# DDR3.net
KiCad netlist of a schematic drawn in Altium Designer
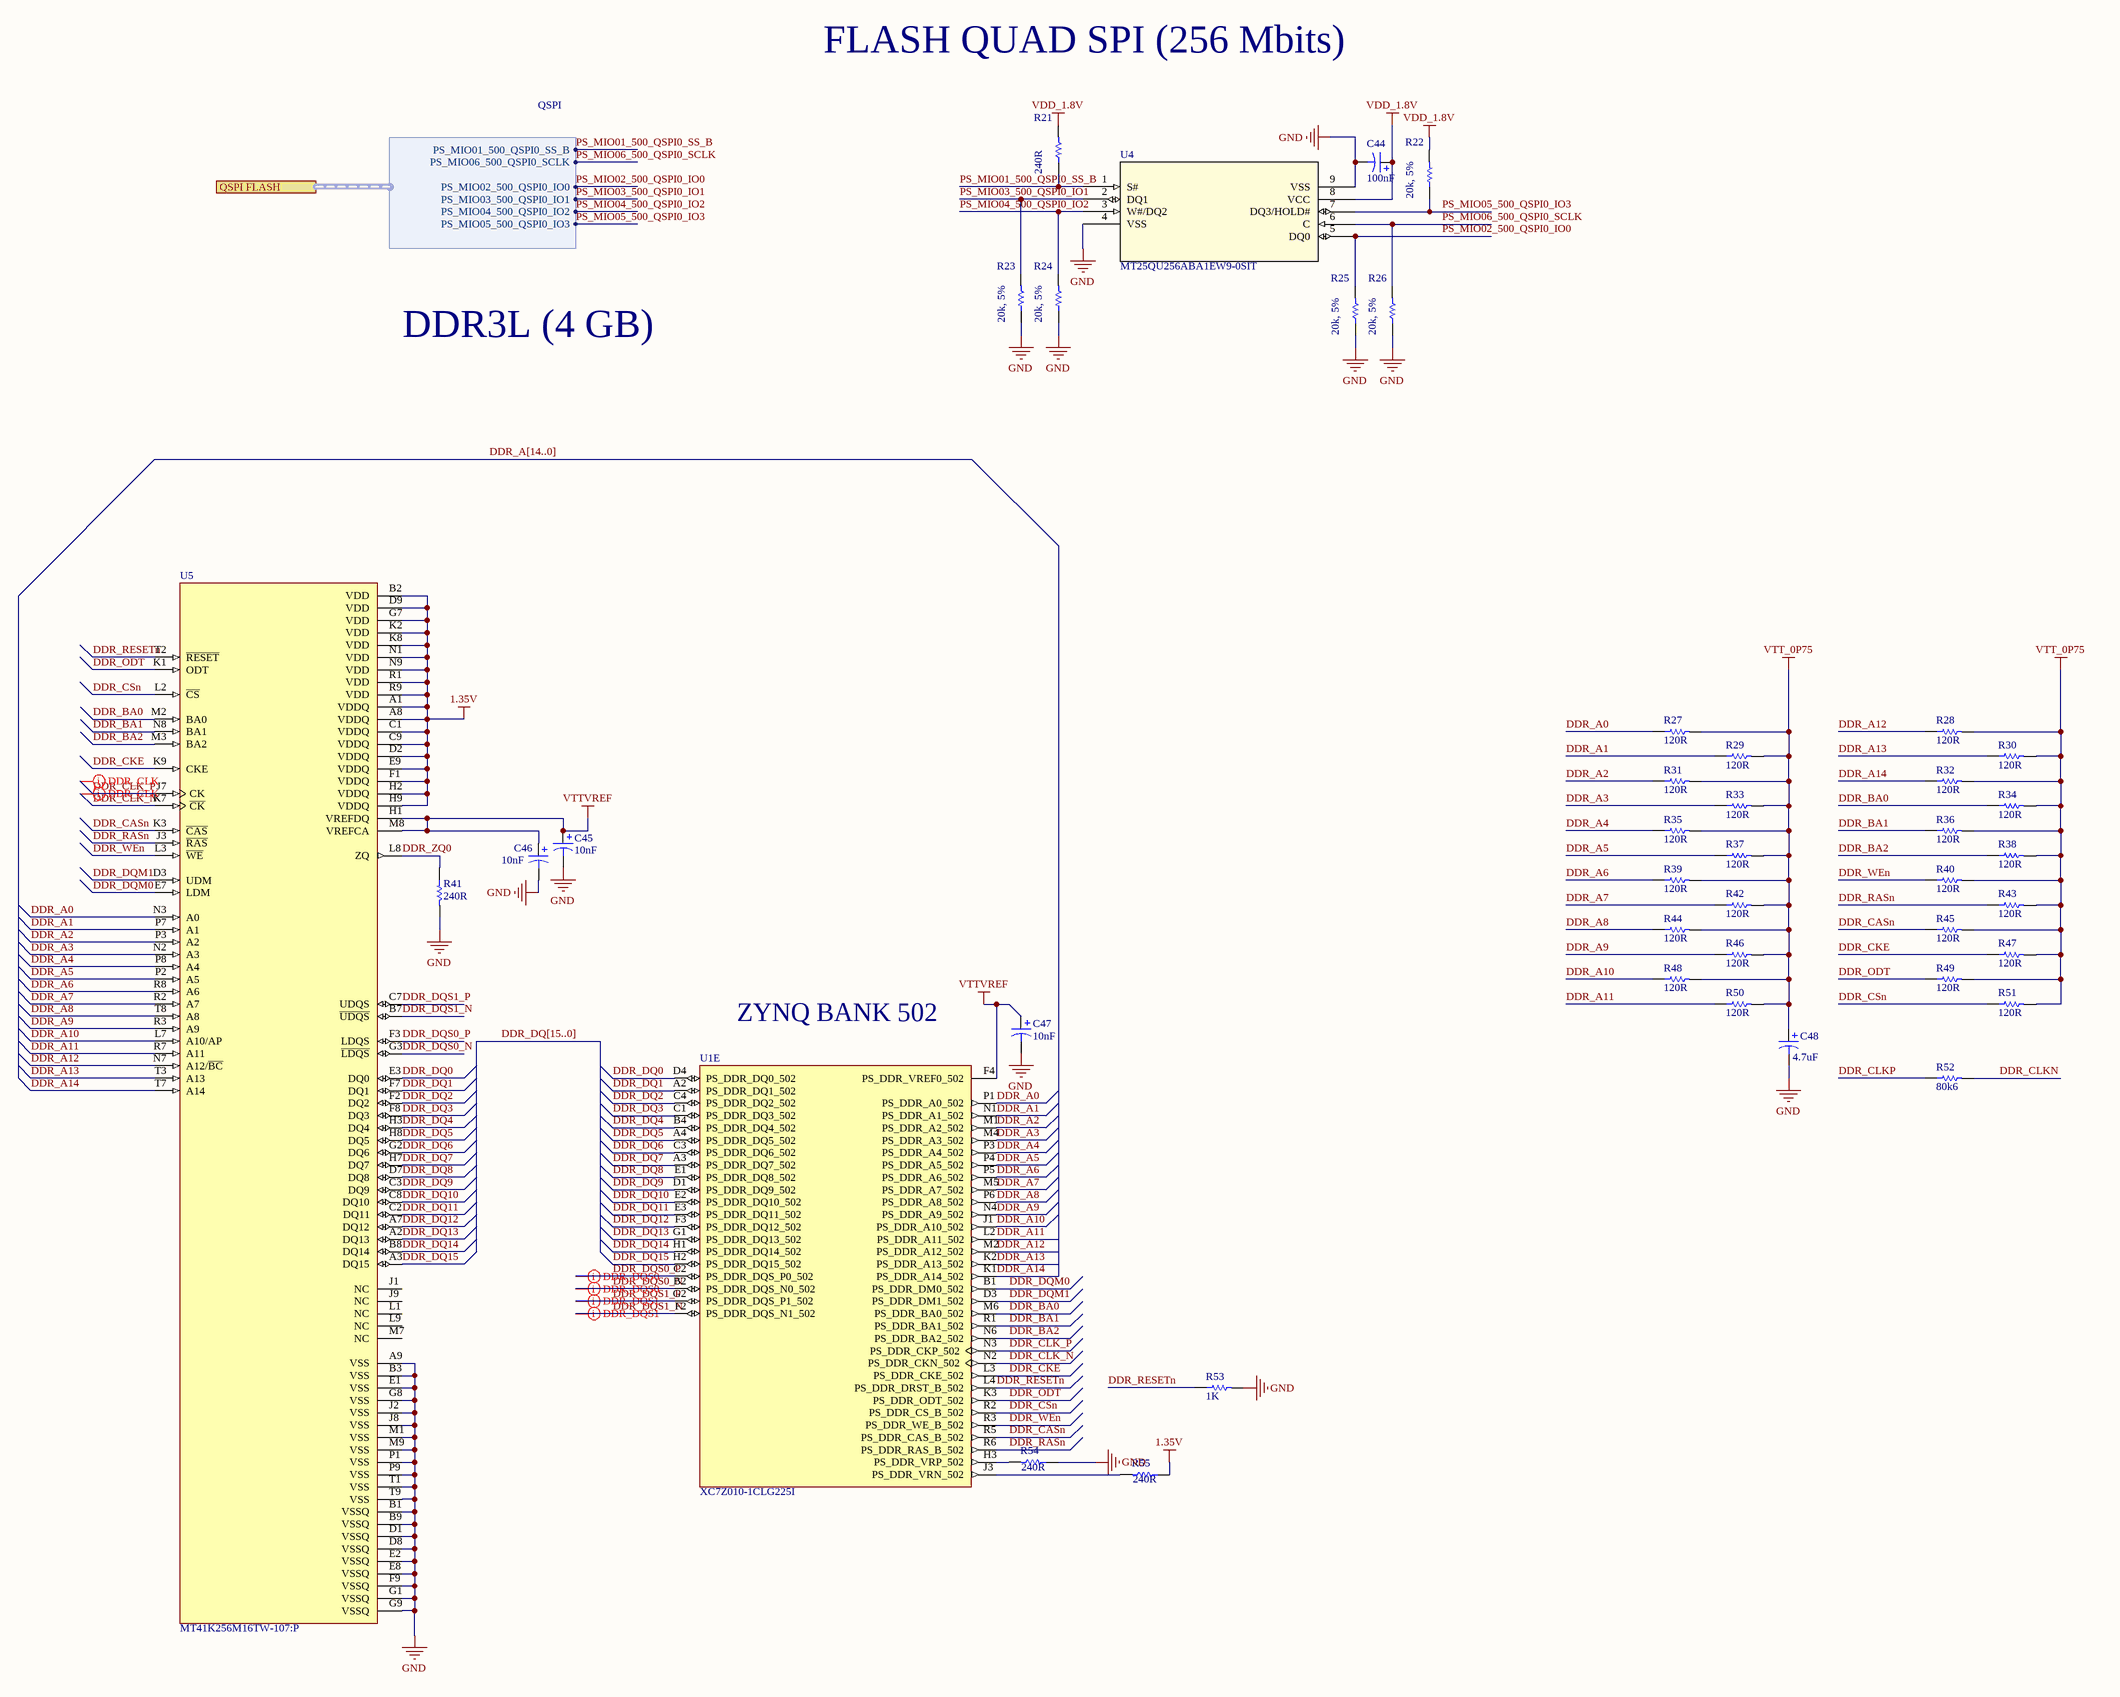
[diagram p0: DDR3.SchDoc]

(export (version "E")
  (design (tool "Eeschema 10.0.6"))
  (components
    (comp (ref "C44")
      (value "100nF")
      (footprint "C0805")
      (description "Polarized Capacitor (Surface Mount)")
      (fields (field (name "Comment") "Cap Pol3") (field (name "PUBLISHER") "Altium Limited"))
      (libsource (lib "Miscellaneous Devices") (part "Cap Pol3"))
    )
    (comp (ref "C45")
      (value "10nF")
      (footprint "C0805")
      (description "Polarized Capacitor (Surface Mount)")
      (fields (field (name "Comment") "Cap Pol3") (field (name "PUBLISHER") "Altium Limited"))
      (libsource (lib "Miscellaneous Devices") (part "Cap Pol3"))
    )
    (comp (ref "C46")
      (value "10nF")
      (footprint "C0805")
      (description "Polarized Capacitor (Surface Mount)")
      (fields (field (name "Comment") "Cap Pol3") (field (name "PUBLISHER") "Altium Limited"))
      (libsource (lib "Miscellaneous Devices") (part "Cap Pol3"))
    )
    (comp (ref "C47")
      (value "10nF")
      (footprint "C0805")
      (description "Polarized Capacitor (Surface Mount)")
      (fields (field (name "Comment") "Cap Pol3") (field (name "PUBLISHER") "Altium Limited"))
      (libsource (lib "Miscellaneous Devices") (part "Cap Pol3"))
    )
    (comp (ref "C48")
      (value "4.7uF")
      (footprint "C0805")
      (description "Polarized Capacitor (Surface Mount)")
      (fields (field (name "Comment") "Cap Pol3") (field (name "PUBLISHER") "Altium Limited"))
      (libsource (lib "Miscellaneous Devices") (part "Cap Pol3"))
    )
    (comp (ref "R21")
      (value "240R")
      (footprint "0603")
      (description "Resistor")
      (fields
        (field (name "MANUFACTURER") "Generic Components")
        (field (name "Comment") "Res1")
        (field (name "PUBLISHER") "Altium Limited")
      )
      (libsource (lib "lib_protel_HC") (part "Res1_1"))
    )
    (comp (ref "R22")
      (value "20k, 5%")
      (footprint "0603")
      (description "Resistor")
      (fields
        (field (name "MANUFACTURER") "Generic Components")
        (field (name "Comment") "Res1")
        (field (name "PUBLISHER") "Altium Limited")
      )
      (libsource (lib "lib_protel_HC") (part "Res1_1"))
    )
    (comp (ref "R23")
      (value "20k, 5%")
      (footprint "0603")
      (description "Resistor")
      (fields
        (field (name "MANUFACTURER") "Generic Components")
        (field (name "Comment") "Res1")
        (field (name "PUBLISHER") "Altium Limited")
      )
      (libsource (lib "lib_protel_HC") (part "Res1_1"))
    )
    (comp (ref "R24")
      (value "20k, 5%")
      (footprint "0603")
      (description "Resistor")
      (fields
        (field (name "MANUFACTURER") "Generic Components")
        (field (name "Comment") "Res1")
        (field (name "PUBLISHER") "Altium Limited")
      )
      (libsource (lib "lib_protel_HC") (part "Res1_1"))
    )
    (comp (ref "R25")
      (value "20k, 5%")
      (footprint "0603")
      (description "Resistor")
      (fields
        (field (name "MANUFACTURER") "Generic Components")
        (field (name "Comment") "Res1")
        (field (name "PUBLISHER") "Altium Limited")
      )
      (libsource (lib "lib_protel_HC") (part "Res1_1"))
    )
    (comp (ref "R26")
      (value "20k, 5%")
      (footprint "0603")
      (description "Resistor")
      (fields
        (field (name "MANUFACTURER") "Generic Components")
        (field (name "Comment") "Res1")
        (field (name "PUBLISHER") "Altium Limited")
      )
      (libsource (lib "lib_protel_HC") (part "Res1_1"))
    )
    (comp (ref "R27")
      (value "120R")
      (footprint "0603")
      (description "Resistor")
      (fields
        (field (name "MANUFACTURER") "Generic Components")
        (field (name "Comment") "Res1")
        (field (name "PUBLISHER") "Altium Limited")
      )
      (libsource (lib "lib_protel_HC") (part "Res1_1"))
    )
    (comp (ref "R28")
      (value "120R")
      (footprint "0603")
      (description "Resistor")
      (fields
        (field (name "MANUFACTURER") "Generic Components")
        (field (name "Comment") "Res1")
        (field (name "PUBLISHER") "Altium Limited")
      )
      (libsource (lib "lib_protel_HC") (part "Res1_1"))
    )
    (comp (ref "R29")
      (value "120R")
      (footprint "0603")
      (description "Resistor")
      (fields
        (field (name "MANUFACTURER") "Generic Components")
        (field (name "Comment") "Res1")
        (field (name "PUBLISHER") "Altium Limited")
      )
      (libsource (lib "lib_protel_HC") (part "Res1_1"))
    )
    (comp (ref "R30")
      (value "120R")
      (footprint "0603")
      (description "Resistor")
      (fields
        (field (name "MANUFACTURER") "Generic Components")
        (field (name "Comment") "Res1")
        (field (name "PUBLISHER") "Altium Limited")
      )
      (libsource (lib "lib_protel_HC") (part "Res1_1"))
    )
    (comp (ref "R31")
      (value "120R")
      (footprint "0603")
      (description "Resistor")
      (fields
        (field (name "MANUFACTURER") "Generic Components")
        (field (name "Comment") "Res1")
        (field (name "PUBLISHER") "Altium Limited")
      )
      (libsource (lib "lib_protel_HC") (part "Res1_1"))
    )
    (comp (ref "R32")
      (value "120R")
      (footprint "0603")
      (description "Resistor")
      (fields
        (field (name "MANUFACTURER") "Generic Components")
        (field (name "Comment") "Res1")
        (field (name "PUBLISHER") "Altium Limited")
      )
      (libsource (lib "lib_protel_HC") (part "Res1_1"))
    )
    (comp (ref "R33")
      (value "120R")
      (footprint "0603")
      (description "Resistor")
      (fields
        (field (name "MANUFACTURER") "Generic Components")
        (field (name "Comment") "Res1")
        (field (name "PUBLISHER") "Altium Limited")
      )
      (libsource (lib "lib_protel_HC") (part "Res1_1"))
    )
    (comp (ref "R34")
      (value "120R")
      (footprint "0603")
      (description "Resistor")
      (fields
        (field (name "MANUFACTURER") "Generic Components")
        (field (name "Comment") "Res1")
        (field (name "PUBLISHER") "Altium Limited")
      )
      (libsource (lib "lib_protel_HC") (part "Res1_1"))
    )
    (comp (ref "R35")
      (value "120R")
      (footprint "0603")
      (description "Resistor")
      (fields
        (field (name "MANUFACTURER") "Generic Components")
        (field (name "Comment") "Res1")
        (field (name "PUBLISHER") "Altium Limited")
      )
      (libsource (lib "lib_protel_HC") (part "Res1_1"))
    )
    (comp (ref "R36")
      (value "120R")
      (footprint "0603")
      (description "Resistor")
      (fields
        (field (name "MANUFACTURER") "Generic Components")
        (field (name "Comment") "Res1")
        (field (name "PUBLISHER") "Altium Limited")
      )
      (libsource (lib "lib_protel_HC") (part "Res1_1"))
    )
    (comp (ref "R37")
      (value "120R")
      (footprint "0603")
      (description "Resistor")
      (fields
        (field (name "MANUFACTURER") "Generic Components")
        (field (name "Comment") "Res1")
        (field (name "PUBLISHER") "Altium Limited")
      )
      (libsource (lib "lib_protel_HC") (part "Res1_1"))
    )
    (comp (ref "R38")
      (value "120R")
      (footprint "0603")
      (description "Resistor")
      (fields
        (field (name "MANUFACTURER") "Generic Components")
        (field (name "Comment") "Res1")
        (field (name "PUBLISHER") "Altium Limited")
      )
      (libsource (lib "lib_protel_HC") (part "Res1_1"))
    )
    (comp (ref "R39")
      (value "120R")
      (footprint "0603")
      (description "Resistor")
      (fields
        (field (name "MANUFACTURER") "Generic Components")
        (field (name "Comment") "Res1")
        (field (name "PUBLISHER") "Altium Limited")
      )
      (libsource (lib "lib_protel_HC") (part "Res1_1"))
    )
    (comp (ref "R40")
      (value "120R")
      (footprint "0603")
      (description "Resistor")
      (fields
        (field (name "MANUFACTURER") "Generic Components")
        (field (name "Comment") "Res1")
        (field (name "PUBLISHER") "Altium Limited")
      )
      (libsource (lib "lib_protel_HC") (part "Res1_1"))
    )
    (comp (ref "R41")
      (value "240R")
      (footprint "0603")
      (description "Resistor")
      (fields
        (field (name "MANUFACTURER") "Generic Components")
        (field (name "Comment") "Res1")
        (field (name "PUBLISHER") "Altium Limited")
      )
      (libsource (lib "lib_protel_HC") (part "Res1_1"))
    )
    (comp (ref "R42")
      (value "120R")
      (footprint "0603")
      (description "Resistor")
      (fields
        (field (name "MANUFACTURER") "Generic Components")
        (field (name "Comment") "Res1")
        (field (name "PUBLISHER") "Altium Limited")
      )
      (libsource (lib "lib_protel_HC") (part "Res1_1"))
    )
    (comp (ref "R43")
      (value "120R")
      (footprint "0603")
      (description "Resistor")
      (fields
        (field (name "MANUFACTURER") "Generic Components")
        (field (name "Comment") "Res1")
        (field (name "PUBLISHER") "Altium Limited")
      )
      (libsource (lib "lib_protel_HC") (part "Res1_1"))
    )
    (comp (ref "R44")
      (value "120R")
      (footprint "0603")
      (description "Resistor")
      (fields
        (field (name "MANUFACTURER") "Generic Components")
        (field (name "Comment") "Res1")
        (field (name "PUBLISHER") "Altium Limited")
      )
      (libsource (lib "lib_protel_HC") (part "Res1_1"))
    )
    (comp (ref "R45")
      (value "120R")
      (footprint "0603")
      (description "Resistor")
      (fields
        (field (name "MANUFACTURER") "Generic Components")
        (field (name "Comment") "Res1")
        (field (name "PUBLISHER") "Altium Limited")
      )
      (libsource (lib "lib_protel_HC") (part "Res1_1"))
    )
    (comp (ref "R46")
      (value "120R")
      (footprint "0603")
      (description "Resistor")
      (fields
        (field (name "MANUFACTURER") "Generic Components")
        (field (name "Comment") "Res1")
        (field (name "PUBLISHER") "Altium Limited")
      )
      (libsource (lib "lib_protel_HC") (part "Res1_1"))
    )
    (comp (ref "R47")
      (value "120R")
      (footprint "0603")
      (description "Resistor")
      (fields
        (field (name "MANUFACTURER") "Generic Components")
        (field (name "Comment") "Res1")
        (field (name "PUBLISHER") "Altium Limited")
      )
      (libsource (lib "lib_protel_HC") (part "Res1_1"))
    )
    (comp (ref "R48")
      (value "120R")
      (footprint "0603")
      (description "Resistor")
      (fields
        (field (name "MANUFACTURER") "Generic Components")
        (field (name "Comment") "Res1")
        (field (name "PUBLISHER") "Altium Limited")
      )
      (libsource (lib "lib_protel_HC") (part "Res1_1"))
    )
    (comp (ref "R49")
      (value "120R")
      (footprint "0603")
      (description "Resistor")
      (fields
        (field (name "MANUFACTURER") "Generic Components")
        (field (name "Comment") "Res1")
        (field (name "PUBLISHER") "Altium Limited")
      )
      (libsource (lib "lib_protel_HC") (part "Res1_1"))
    )
    (comp (ref "R50")
      (value "120R")
      (footprint "0603")
      (description "Resistor")
      (fields
        (field (name "MANUFACTURER") "Generic Components")
        (field (name "Comment") "Res1")
        (field (name "PUBLISHER") "Altium Limited")
      )
      (libsource (lib "lib_protel_HC") (part "Res1_1"))
    )
    (comp (ref "R51")
      (value "120R")
      (footprint "0603")
      (description "Resistor")
      (fields
        (field (name "MANUFACTURER") "Generic Components")
        (field (name "Comment") "Res1")
        (field (name "PUBLISHER") "Altium Limited")
      )
      (libsource (lib "lib_protel_HC") (part "Res1_1"))
    )
    (comp (ref "R52")
      (value "80k6")
      (footprint "0603")
      (description "Resistor")
      (fields
        (field (name "MANUFACTURER") "Generic Components")
        (field (name "Comment") "Res1")
        (field (name "PUBLISHER") "Altium Limited")
      )
      (libsource (lib "lib_protel_HC") (part "Res1_1"))
    )
    (comp (ref "R53")
      (value "1K")
      (footprint "0603")
      (description "Resistor")
      (fields
        (field (name "MANUFACTURER") "Generic Components")
        (field (name "Comment") "Res1")
        (field (name "PUBLISHER") "Altium Limited")
      )
      (libsource (lib "lib_protel_HC") (part "Res1_1"))
    )
    (comp (ref "R54")
      (value "240R")
      (footprint "0603")
      (description "Resistor")
      (fields
        (field (name "MANUFACTURER") "Generic Components")
        (field (name "Comment") "Res1")
        (field (name "PUBLISHER") "Altium Limited")
      )
      (libsource (lib "lib_protel_HC") (part "Res1_1"))
    )
    (comp (ref "R55")
      (value "240R")
      (footprint "0603")
      (description "Resistor")
      (fields
        (field (name "MANUFACTURER") "Generic Components")
        (field (name "Comment") "Res1")
        (field (name "PUBLISHER") "Altium Limited")
      )
      (libsource (lib "lib_protel_HC") (part "Res1_1"))
    )
    (comp (ref "U1")
      (value "XC7Z010-1CLG225I")
      (footprint "BGA225C80P15X15_1300X1300X150N")
      (fields (field (name "MF") "Xilinx Inc."))
      (libsource (lib "XC7Z010-1CLG225I") (part "XC7Z010-1CLG225I"))
    )
    (comp (ref "U4")
      (value "MT25QU256ABA1EW9-0SIT")
      (footprint "W-PDFN-8MLP8_8X6_MRN")
      (description "No Description Available")
      (libsource (lib "MT25QU256ABA1EW9-0SIT") (part "MT25QU256ABA1EW9-0SIT"))
    )
    (comp (ref "U5")
      (value "MT41K256M16TW-107:P")
      (footprint "BGA96C80P9X16_1400X800X120")
      (fields (field (name "MF") "{'manufacturer': u'Micron Technology Inc.'}"))
      (libsource (lib "MT41K256M16TW-107_P") (part "MT41K256M16TW-107{colon}P"))
    )
  )
  (nets
    (net (code "2") (name "/DDR_A0") (class "Default")
      (node (ref "R27") (pin "1") (pinfunction "1_1") (pintype "passive"))
      (node (ref "U1") (pin "P1") (pinfunction "PS_DDR_A0_502_P1") (pintype "output"))
      (node (ref "U5") (pin "N3") (pinfunction "A0_N3") (pintype "input"))
    )
    (net (code "3") (name "/DDR_A1") (class "Default")
      (node (ref "R29") (pin "1") (pinfunction "1_1") (pintype "passive"))
      (node (ref "U1") (pin "N1") (pinfunction "PS_DDR_A1_502_N1") (pintype "output"))
      (node (ref "U5") (pin "P7") (pinfunction "A1_P7") (pintype "input"))
    )
    (net (code "4") (name "/DDR_A2") (class "Default")
      (node (ref "R31") (pin "1") (pinfunction "1_1") (pintype "passive"))
      (node (ref "U1") (pin "M1") (pinfunction "PS_DDR_A2_502_M1") (pintype "output"))
      (node (ref "U5") (pin "P3") (pinfunction "A2_P3") (pintype "input"))
    )
    (net (code "5") (name "/DDR_A3") (class "Default")
      (node (ref "R33") (pin "1") (pinfunction "1_1") (pintype "passive"))
      (node (ref "U1") (pin "M4") (pinfunction "PS_DDR_A3_502_M4") (pintype "output"))
      (node (ref "U5") (pin "N2") (pinfunction "A3_N2") (pintype "input"))
    )
    (net (code "6") (name "/DDR_A4") (class "Default")
      (node (ref "R35") (pin "1") (pinfunction "1_1") (pintype "passive"))
      (node (ref "U1") (pin "P3") (pinfunction "PS_DDR_A4_502_P3") (pintype "output"))
      (node (ref "U5") (pin "P8") (pinfunction "A4_P8") (pintype "input"))
    )
    (net (code "7") (name "/DDR_A5") (class "Default")
      (node (ref "R37") (pin "1") (pinfunction "1_1") (pintype "passive"))
      (node (ref "U1") (pin "P4") (pinfunction "PS_DDR_A5_502_P4") (pintype "output"))
      (node (ref "U5") (pin "P2") (pinfunction "A5_P2") (pintype "input"))
    )
    (net (code "8") (name "/DDR_A6") (class "Default")
      (node (ref "R39") (pin "1") (pinfunction "1_1") (pintype "passive"))
      (node (ref "U1") (pin "P5") (pinfunction "PS_DDR_A6_502_P5") (pintype "output"))
      (node (ref "U5") (pin "R8") (pinfunction "A6_R8") (pintype "input"))
    )
    (net (code "9") (name "/DDR_A7") (class "Default")
      (node (ref "R42") (pin "1") (pinfunction "1_1") (pintype "passive"))
      (node (ref "U1") (pin "M5") (pinfunction "PS_DDR_A7_502_M5") (pintype "output"))
      (node (ref "U5") (pin "R2") (pinfunction "A7_R2") (pintype "input"))
    )
    (net (code "10") (name "/DDR_A8") (class "Default")
      (node (ref "R44") (pin "1") (pinfunction "1_1") (pintype "passive"))
      (node (ref "U1") (pin "P6") (pinfunction "PS_DDR_A8_502_P6") (pintype "output"))
      (node (ref "U5") (pin "T8") (pinfunction "A8_T8") (pintype "input"))
    )
    (net (code "11") (name "/DDR_A9") (class "Default")
      (node (ref "R46") (pin "1") (pinfunction "1_1") (pintype "passive"))
      (node (ref "U1") (pin "N4") (pinfunction "PS_DDR_A9_502_N4") (pintype "output"))
      (node (ref "U5") (pin "R3") (pinfunction "A9_R3") (pintype "input"))
    )
    (net (code "12") (name "/DDR_A10") (class "Default")
      (node (ref "R48") (pin "1") (pinfunction "1_1") (pintype "passive"))
      (node (ref "U1") (pin "J1") (pinfunction "PS_DDR_A10_502_J1") (pintype "output"))
      (node (ref "U5") (pin "L7") (pinfunction "A10/AP_L7") (pintype "input"))
    )
    (net (code "13") (name "/DDR_A11") (class "Default")
      (node (ref "R50") (pin "1") (pinfunction "1_1") (pintype "passive"))
      (node (ref "U1") (pin "L2") (pinfunction "PS_DDR_A11_502_L2") (pintype "output"))
      (node (ref "U5") (pin "R7") (pinfunction "A11_R7") (pintype "input"))
    )
    (net (code "14") (name "/DDR_A12") (class "Default")
      (node (ref "R28") (pin "1") (pinfunction "1_1") (pintype "passive"))
      (node (ref "U1") (pin "M2") (pinfunction "PS_DDR_A12_502_M2") (pintype "output"))
      (node (ref "U5") (pin "N7") (pinfunction "A12/~{BC}_N7") (pintype "input"))
    )
    (net (code "15") (name "/DDR_A13") (class "Default")
      (node (ref "R30") (pin "1") (pinfunction "1_1") (pintype "passive"))
      (node (ref "U1") (pin "K2") (pinfunction "PS_DDR_A13_502_K2") (pintype "output"))
      (node (ref "U5") (pin "T3") (pinfunction "A13_T3") (pintype "input"))
    )
    (net (code "16") (name "/DDR_A14") (class "Default")
      (node (ref "R32") (pin "1") (pinfunction "1_1") (pintype "passive"))
      (node (ref "U1") (pin "K1") (pinfunction "PS_DDR_A14_502_K1") (pintype "output"))
      (node (ref "U5") (pin "T7") (pinfunction "A14_T7") (pintype "input"))
    )
    (net (code "18") (name "/DDR_BA0") (class "Default")
      (node (ref "R34") (pin "1") (pinfunction "1_1") (pintype "passive"))
      (node (ref "U1") (pin "M6") (pinfunction "PS_DDR_BA0_502_M6") (pintype "output"))
      (node (ref "U5") (pin "M2") (pinfunction "BA0_M2") (pintype "input"))
    )
    (net (code "19") (name "/DDR_BA1") (class "Default")
      (node (ref "R36") (pin "1") (pinfunction "1_1") (pintype "passive"))
      (node (ref "U1") (pin "R1") (pinfunction "PS_DDR_BA1_502_R1") (pintype "output"))
      (node (ref "U5") (pin "N8") (pinfunction "BA1_N8") (pintype "input"))
    )
    (net (code "20") (name "/DDR_BA2") (class "Default")
      (node (ref "R38") (pin "1") (pinfunction "1_1") (pintype "passive"))
      (node (ref "U1") (pin "N6") (pinfunction "PS_DDR_BA2_502_N6") (pintype "output"))
      (node (ref "U5") (pin "M3") (pinfunction "BA2_M3") (pintype "input"))
    )
    (net (code "21") (name "/DDR_CASn") (class "Default")
      (node (ref "R45") (pin "1") (pinfunction "1_1") (pintype "passive"))
      (node (ref "U1") (pin "R5") (pinfunction "PS_DDR_CAS_B_502_R5") (pintype "output"))
      (node (ref "U5") (pin "K3") (pinfunction "~{CAS}_K3") (pintype "input"))
    )
    (net (code "22") (name "/DDR_CKE") (class "Default")
      (node (ref "R47") (pin "1") (pinfunction "1_1") (pintype "passive"))
      (node (ref "U1") (pin "L3") (pinfunction "PS_DDR_CKE_502_L3") (pintype "output"))
      (node (ref "U5") (pin "K9") (pinfunction "CKE_K9") (pintype "input"))
    )
    (net (code "23") (name "/DDR_CLKN") (class "Default")
      (node (ref "R52") (pin "2") (pinfunction "2_2") (pintype "passive"))
    )
    (net (code "24") (name "/DDR_CLKP") (class "Default")
      (node (ref "R52") (pin "1") (pinfunction "1_1") (pintype "passive"))
    )
    (net (code "25") (name "/DDR_CLK_N") (class "Default")
      (node (ref "U1") (pin "N2") (pinfunction "PS_DDR_CKN_502_N2") (pintype "output"))
      (node (ref "U5") (pin "K7") (pinfunction "~{CK}_K7") (pintype "input"))
    )
    (net (code "26") (name "/DDR_CLK_P") (class "Default")
      (node (ref "U1") (pin "N3") (pinfunction "PS_DDR_CKP_502_N3") (pintype "output"))
      (node (ref "U5") (pin "J7") (pinfunction "CK_J7") (pintype "input"))
    )
    (net (code "27") (name "/DDR_CSn") (class "Default")
      (node (ref "R51") (pin "1") (pinfunction "1_1") (pintype "passive"))
      (node (ref "U1") (pin "R2") (pinfunction "PS_DDR_CS_B_502_R2") (pintype "output"))
      (node (ref "U5") (pin "L2") (pinfunction "~{CS}_L2") (pintype "input"))
    )
    (net (code "28") (name "/DDR_DQ0") (class "Default")
      (node (ref "U1") (pin "D4") (pinfunction "PS_DDR_DQ0_502_D4") (pintype "bidirectional"))
      (node (ref "U5") (pin "E3") (pinfunction "DQ0_E3") (pintype "bidirectional"))
    )
    (net (code "29") (name "/DDR_DQ1") (class "Default")
      (node (ref "U1") (pin "A2") (pinfunction "PS_DDR_DQ1_502_A2") (pintype "bidirectional"))
      (node (ref "U5") (pin "F7") (pinfunction "DQ1_F7") (pintype "bidirectional"))
    )
    (net (code "30") (name "/DDR_DQ2") (class "Default")
      (node (ref "U1") (pin "C4") (pinfunction "PS_DDR_DQ2_502_C4") (pintype "bidirectional"))
      (node (ref "U5") (pin "F2") (pinfunction "DQ2_F2") (pintype "bidirectional"))
    )
    (net (code "31") (name "/DDR_DQ3") (class "Default")
      (node (ref "U1") (pin "C1") (pinfunction "PS_DDR_DQ3_502_C1") (pintype "bidirectional"))
      (node (ref "U5") (pin "F8") (pinfunction "DQ3_F8") (pintype "bidirectional"))
    )
    (net (code "32") (name "/DDR_DQ4") (class "Default")
      (node (ref "U1") (pin "B4") (pinfunction "PS_DDR_DQ4_502_B4") (pintype "bidirectional"))
      (node (ref "U5") (pin "H3") (pinfunction "DQ4_H3") (pintype "bidirectional"))
    )
    (net (code "33") (name "/DDR_DQ5") (class "Default")
      (node (ref "U1") (pin "A4") (pinfunction "PS_DDR_DQ5_502_A4") (pintype "bidirectional"))
      (node (ref "U5") (pin "H8") (pinfunction "DQ5_H8") (pintype "bidirectional"))
    )
    (net (code "34") (name "/DDR_DQ6") (class "Default")
      (node (ref "U1") (pin "C3") (pinfunction "PS_DDR_DQ6_502_C3") (pintype "bidirectional"))
      (node (ref "U5") (pin "G2") (pinfunction "DQ6_G2") (pintype "bidirectional"))
    )
    (net (code "35") (name "/DDR_DQ7") (class "Default")
      (node (ref "U1") (pin "A3") (pinfunction "PS_DDR_DQ7_502_A3") (pintype "bidirectional"))
      (node (ref "U5") (pin "H7") (pinfunction "DQ7_H7") (pintype "bidirectional"))
    )
    (net (code "36") (name "/DDR_DQ8") (class "Default")
      (node (ref "U1") (pin "E1") (pinfunction "PS_DDR_DQ8_502_E1") (pintype "bidirectional"))
      (node (ref "U5") (pin "D7") (pinfunction "DQ8_D7") (pintype "bidirectional"))
    )
    (net (code "37") (name "/DDR_DQ9") (class "Default")
      (node (ref "U1") (pin "D1") (pinfunction "PS_DDR_DQ9_502_D1") (pintype "bidirectional"))
      (node (ref "U5") (pin "C3") (pinfunction "DQ9_C3") (pintype "bidirectional"))
    )
    (net (code "38") (name "/DDR_DQ10") (class "Default")
      (node (ref "U1") (pin "E2") (pinfunction "PS_DDR_DQ10_502_E2") (pintype "bidirectional"))
      (node (ref "U5") (pin "C8") (pinfunction "DQ10_C8") (pintype "bidirectional"))
    )
    (net (code "39") (name "/DDR_DQ11") (class "Default")
      (node (ref "U1") (pin "E3") (pinfunction "PS_DDR_DQ11_502_E3") (pintype "bidirectional"))
      (node (ref "U5") (pin "C2") (pinfunction "DQ11_C2") (pintype "bidirectional"))
    )
    (net (code "40") (name "/DDR_DQ12") (class "Default")
      (node (ref "U1") (pin "F3") (pinfunction "PS_DDR_DQ12_502_F3") (pintype "bidirectional"))
      (node (ref "U5") (pin "A7") (pinfunction "DQ12_A7") (pintype "bidirectional"))
    )
    (net (code "41") (name "/DDR_DQ13") (class "Default")
      (node (ref "U1") (pin "G1") (pinfunction "PS_DDR_DQ13_502_G1") (pintype "bidirectional"))
      (node (ref "U5") (pin "A2") (pinfunction "DQ13_A2") (pintype "bidirectional"))
    )
    (net (code "42") (name "/DDR_DQ14") (class "Default")
      (node (ref "U1") (pin "H1") (pinfunction "PS_DDR_DQ14_502_H1") (pintype "bidirectional"))
      (node (ref "U5") (pin "B8") (pinfunction "DQ14_B8") (pintype "bidirectional"))
    )
    (net (code "43") (name "/DDR_DQ15") (class "Default")
      (node (ref "U1") (pin "H2") (pinfunction "PS_DDR_DQ15_502_H2") (pintype "bidirectional"))
      (node (ref "U5") (pin "A3") (pinfunction "DQ15_A3") (pintype "bidirectional"))
    )
    (net (code "44") (name "/DDR_DQM0") (class "Default")
      (node (ref "U1") (pin "B1") (pinfunction "PS_DDR_DM0_502_B1") (pintype "output"))
      (node (ref "U5") (pin "E7") (pinfunction "LDM_E7") (pintype "input"))
    )
    (net (code "45") (name "/DDR_DQM1") (class "Default")
      (node (ref "U1") (pin "D3") (pinfunction "PS_DDR_DM1_502_D3") (pintype "output"))
      (node (ref "U5") (pin "D3") (pinfunction "UDM_D3") (pintype "input"))
    )
    (net (code "46") (name "/DDR_DQS0_N") (class "Default")
      (node (ref "U1") (pin "B2") (pinfunction "PS_DDR_DQS_N0_502_B2") (pintype "bidirectional"))
      (node (ref "U5") (pin "G3") (pinfunction "~{LDQS}_G3") (pintype "bidirectional"))
    )
    (net (code "47") (name "/DDR_DQS0_P") (class "Default")
      (node (ref "U1") (pin "C2") (pinfunction "PS_DDR_DQS_P0_502_C2") (pintype "bidirectional"))
      (node (ref "U5") (pin "F3") (pinfunction "LDQS_F3") (pintype "bidirectional"))
    )
    (net (code "48") (name "/DDR_DQS1_N") (class "Default")
      (node (ref "U1") (pin "F2") (pinfunction "PS_DDR_DQS_N1_502_F2") (pintype "bidirectional"))
      (node (ref "U5") (pin "B7") (pinfunction "~{UDQS}_B7") (pintype "bidirectional"))
    )
    (net (code "49") (name "/DDR_DQS1_P") (class "Default")
      (node (ref "U1") (pin "G2") (pinfunction "PS_DDR_DQS_P1_502_G2") (pintype "bidirectional"))
      (node (ref "U5") (pin "C7") (pinfunction "UDQS_C7") (pintype "bidirectional"))
    )
    (net (code "51") (name "/DDR_ODT") (class "Default")
      (node (ref "R49") (pin "1") (pinfunction "1_1") (pintype "passive"))
      (node (ref "U1") (pin "K3") (pinfunction "PS_DDR_ODT_502_K3") (pintype "output"))
      (node (ref "U5") (pin "K1") (pinfunction "ODT_K1") (pintype "input"))
    )
    (net (code "52") (name "/DDR_RASn") (class "Default")
      (node (ref "R43") (pin "1") (pinfunction "1_1") (pintype "passive"))
      (node (ref "U1") (pin "R6") (pinfunction "PS_DDR_RAS_B_502_R6") (pintype "output"))
      (node (ref "U5") (pin "J3") (pinfunction "~{RAS}_J3") (pintype "input"))
    )
    (net (code "53") (name "/DDR_RESETn") (class "Default")
      (node (ref "R53") (pin "1") (pinfunction "1_1") (pintype "passive"))
      (node (ref "U1") (pin "L4") (pinfunction "PS_DDR_DRST_B_502_L4") (pintype "output"))
      (node (ref "U5") (pin "T2") (pinfunction "~{RESET}_T2") (pintype "input"))
    )
    (net (code "54") (name "/DDR_WEn") (class "Default")
      (node (ref "R40") (pin "1") (pinfunction "1_1") (pintype "passive"))
      (node (ref "U1") (pin "R3") (pinfunction "PS_DDR_WE_B_502_R3") (pintype "output"))
      (node (ref "U5") (pin "L3") (pinfunction "~{WE}_L3") (pintype "input"))
    )
    (net (code "55") (name "/DDR_ZQ0") (class "Default")
      (node (ref "R41") (pin "1") (pinfunction "1_1") (pintype "passive"))
      (node (ref "U5") (pin "L8") (pinfunction "ZQ_L8") (pintype "output"))
    )
    (net (code "56") (name "/PS_MIO01_500_QSPI0_SS_B") (class "Default")
      (node (ref "R21") (pin "1") (pinfunction "1_1") (pintype "passive"))
      (node (ref "U4") (pin "1") (pinfunction "S#_1") (pintype "input"))
    )
    (net (code "57") (name "/PS_MIO02_500_QSPI0_IO0") (class "Default")
      (node (ref "R25") (pin "2") (pinfunction "2_2") (pintype "passive"))
      (node (ref "U4") (pin "5") (pinfunction "DQ0_5") (pintype "bidirectional"))
    )
    (net (code "58") (name "/PS_MIO03_500_QSPI0_IO1") (class "Default")
      (node (ref "R23") (pin "2") (pinfunction "2_2") (pintype "passive"))
      (node (ref "U4") (pin "2") (pinfunction "DQ1_2") (pintype "bidirectional"))
    )
    (net (code "59") (name "/PS_MIO04_500_QSPI0_IO2") (class "Default")
      (node (ref "R24") (pin "2") (pinfunction "2_2") (pintype "passive"))
      (node (ref "U4") (pin "3") (pinfunction "W#/DQ2_3") (pintype "input"))
    )
    (net (code "60") (name "/PS_MIO05_500_QSPI0_IO3") (class "Default")
      (node (ref "R22") (pin "1") (pinfunction "1_1") (pintype "passive"))
      (node (ref "U4") (pin "7") (pinfunction "DQ3/HOLD#_7") (pintype "bidirectional"))
    )
    (net (code "61") (name "/PS_MIO06_500_QSPI0_SCLK") (class "Default")
      (node (ref "R26") (pin "2") (pinfunction "2_2") (pintype "passive"))
      (node (ref "U4") (pin "6") (pinfunction "C_6") (pintype "input"))
    )
    (net (code "63") (name "1.35V") (class "Default")
      (node (ref "R55") (pin "1") (pinfunction "1_1") (pintype "passive"))
      (node (ref "U5") (pin "A1") (pinfunction "VDDQ_A1") (pintype "power_in"))
      (node (ref "U5") (pin "A8") (pinfunction "VDDQ_A8") (pintype "power_in"))
      (node (ref "U5") (pin "B2") (pinfunction "VDD_B2") (pintype "power_in"))
      (node (ref "U5") (pin "C1") (pinfunction "VDDQ_C1") (pintype "power_in"))
      (node (ref "U5") (pin "C9") (pinfunction "VDDQ_C9") (pintype "power_in"))
      (node (ref "U5") (pin "D2") (pinfunction "VDDQ_D2") (pintype "power_in"))
      (node (ref "U5") (pin "D9") (pinfunction "VDD_D9") (pintype "power_in"))
      (node (ref "U5") (pin "E9") (pinfunction "VDDQ_E9") (pintype "power_in"))
      (node (ref "U5") (pin "F1") (pinfunction "VDDQ_F1") (pintype "power_in"))
      (node (ref "U5") (pin "G7") (pinfunction "VDD_G7") (pintype "power_in"))
      (node (ref "U5") (pin "H2") (pinfunction "VDDQ_H2") (pintype "power_in"))
      (node (ref "U5") (pin "H9") (pinfunction "VDDQ_H9") (pintype "power_in"))
      (node (ref "U5") (pin "K2") (pinfunction "VDD_K2") (pintype "power_in"))
      (node (ref "U5") (pin "K8") (pinfunction "VDD_K8") (pintype "power_in"))
      (node (ref "U5") (pin "N1") (pinfunction "VDD_N1") (pintype "power_in"))
      (node (ref "U5") (pin "N9") (pinfunction "VDD_N9") (pintype "power_in"))
      (node (ref "U5") (pin "R1") (pinfunction "VDD_R1") (pintype "power_in"))
      (node (ref "U5") (pin "R9") (pinfunction "VDD_R9") (pintype "power_in"))
    )
    (net (code "64") (name "GND") (class "Default")
      (node (ref "C44") (pin "2") (pinfunction "2_2") (pintype "passive"))
      (node (ref "C45") (pin "2") (pinfunction "2_2") (pintype "passive"))
      (node (ref "C46") (pin "2") (pinfunction "2_2") (pintype "passive"))
      (node (ref "C47") (pin "2") (pinfunction "2_2") (pintype "passive"))
      (node (ref "C48") (pin "2") (pinfunction "2_2") (pintype "passive"))
      (node (ref "R23") (pin "1") (pinfunction "1_1") (pintype "passive"))
      (node (ref "R24") (pin "1") (pinfunction "1_1") (pintype "passive"))
      (node (ref "R25") (pin "1") (pinfunction "1_1") (pintype "passive"))
      (node (ref "R26") (pin "1") (pinfunction "1_1") (pintype "passive"))
      (node (ref "R41") (pin "2") (pinfunction "2_2") (pintype "passive"))
      (node (ref "R53") (pin "2") (pinfunction "2_2") (pintype "passive"))
      (node (ref "R54") (pin "1") (pinfunction "1_1") (pintype "passive"))
      (node (ref "U4") (pin "4") (pinfunction "VSS_4") (pintype "power_in"))
      (node (ref "U4") (pin "9") (pinfunction "VSS_9") (pintype "power_in"))
      (node (ref "U5") (pin "A9") (pinfunction "VSS_A9") (pintype "power_in"))
      (node (ref "U5") (pin "B1") (pinfunction "VSSQ_B1") (pintype "power_in"))
      (node (ref "U5") (pin "B3") (pinfunction "VSS_B3") (pintype "power_in"))
      (node (ref "U5") (pin "B9") (pinfunction "VSSQ_B9") (pintype "power_in"))
      (node (ref "U5") (pin "D1") (pinfunction "VSSQ_D1") (pintype "power_in"))
      (node (ref "U5") (pin "D8") (pinfunction "VSSQ_D8") (pintype "power_in"))
      (node (ref "U5") (pin "E1") (pinfunction "VSS_E1") (pintype "power_in"))
      (node (ref "U5") (pin "E2") (pinfunction "VSSQ_E2") (pintype "power_in"))
      (node (ref "U5") (pin "E8") (pinfunction "VSSQ_E8") (pintype "power_in"))
      (node (ref "U5") (pin "F9") (pinfunction "VSSQ_F9") (pintype "power_in"))
      (node (ref "U5") (pin "G1") (pinfunction "VSSQ_G1") (pintype "power_in"))
      (node (ref "U5") (pin "G8") (pinfunction "VSS_G8") (pintype "power_in"))
      (node (ref "U5") (pin "G9") (pinfunction "VSSQ_G9") (pintype "power_in"))
      (node (ref "U5") (pin "J2") (pinfunction "VSS_J2") (pintype "power_in"))
      (node (ref "U5") (pin "J8") (pinfunction "VSS_J8") (pintype "power_in"))
      (node (ref "U5") (pin "M1") (pinfunction "VSS_M1") (pintype "power_in"))
      (node (ref "U5") (pin "M9") (pinfunction "VSS_M9") (pintype "power_in"))
      (node (ref "U5") (pin "P1") (pinfunction "VSS_P1") (pintype "power_in"))
      (node (ref "U5") (pin "P9") (pinfunction "VSS_P9") (pintype "power_in"))
      (node (ref "U5") (pin "T1") (pinfunction "VSS_T1") (pintype "power_in"))
      (node (ref "U5") (pin "T9") (pinfunction "VSS_T9") (pintype "power_in"))
    )
    (net (code "65") (name "Net-(U1E-PS_DDR_VRN_502)") (class "Default")
      (node (ref "R55") (pin "2") (pinfunction "2_2") (pintype "passive"))
      (node (ref "U1") (pin "J3") (pinfunction "PS_DDR_VRN_502_J3") (pintype "output"))
    )
    (net (code "66") (name "Net-(U1E-PS_DDR_VRP_502)") (class "Default")
      (node (ref "R54") (pin "2") (pinfunction "2_2") (pintype "passive"))
      (node (ref "U1") (pin "H3") (pinfunction "PS_DDR_VRP_502_H3") (pintype "output"))
    )
    (net (code "67") (name "VDD_1.8V") (class "Default")
      (node (ref "C44") (pin "1") (pinfunction "1_1") (pintype "passive"))
      (node (ref "R21") (pin "2") (pinfunction "2_2") (pintype "passive"))
      (node (ref "R22") (pin "2") (pinfunction "2_2") (pintype "passive"))
      (node (ref "U4") (pin "8") (pinfunction "VCC_8") (pintype "power_in"))
    )
    (net (code "68") (name "VTTVREF") (class "Default")
      (node (ref "C45") (pin "1") (pinfunction "1_1") (pintype "passive"))
      (node (ref "C46") (pin "1") (pinfunction "1_1") (pintype "passive"))
      (node (ref "C47") (pin "1") (pinfunction "1_1") (pintype "passive"))
      (node (ref "U1") (pin "F4") (pinfunction "PS_DDR_VREF0_502_F4") (pintype "power_in"))
      (node (ref "U5") (pin "H1") (pinfunction "VREFDQ_H1") (pintype "power_in"))
      (node (ref "U5") (pin "M8") (pinfunction "VREFCA_M8") (pintype "power_in"))
    )
    (net (code "69") (name "VTT_0P75") (class "Default")
      (node (ref "C48") (pin "1") (pinfunction "1_1") (pintype "passive"))
      (node (ref "R27") (pin "2") (pinfunction "2_2") (pintype "passive"))
      (node (ref "R28") (pin "2") (pinfunction "2_2") (pintype "passive"))
      (node (ref "R29") (pin "2") (pinfunction "2_2") (pintype "passive"))
      (node (ref "R30") (pin "2") (pinfunction "2_2") (pintype "passive"))
      (node (ref "R31") (pin "2") (pinfunction "2_2") (pintype "passive"))
      (node (ref "R32") (pin "2") (pinfunction "2_2") (pintype "passive"))
      (node (ref "R33") (pin "2") (pinfunction "2_2") (pintype "passive"))
      (node (ref "R34") (pin "2") (pinfunction "2_2") (pintype "passive"))
      (node (ref "R35") (pin "2") (pinfunction "2_2") (pintype "passive"))
      (node (ref "R36") (pin "2") (pinfunction "2_2") (pintype "passive"))
      (node (ref "R37") (pin "2") (pinfunction "2_2") (pintype "passive"))
      (node (ref "R38") (pin "2") (pinfunction "2_2") (pintype "passive"))
      (node (ref "R39") (pin "2") (pinfunction "2_2") (pintype "passive"))
      (node (ref "R40") (pin "2") (pinfunction "2_2") (pintype "passive"))
      (node (ref "R42") (pin "2") (pinfunction "2_2") (pintype "passive"))
      (node (ref "R43") (pin "2") (pinfunction "2_2") (pintype "passive"))
      (node (ref "R44") (pin "2") (pinfunction "2_2") (pintype "passive"))
      (node (ref "R45") (pin "2") (pinfunction "2_2") (pintype "passive"))
      (node (ref "R46") (pin "2") (pinfunction "2_2") (pintype "passive"))
      (node (ref "R47") (pin "2") (pinfunction "2_2") (pintype "passive"))
      (node (ref "R48") (pin "2") (pinfunction "2_2") (pintype "passive"))
      (node (ref "R49") (pin "2") (pinfunction "2_2") (pintype "passive"))
      (node (ref "R50") (pin "2") (pinfunction "2_2") (pintype "passive"))
      (node (ref "R51") (pin "2") (pinfunction "2_2") (pintype "passive"))
    )
    (net (code "70") (name "unconnected-(U5-NC-PadJ1)") (class "Default")
      (node (ref "U5") (pin "J1") (pinfunction "NC_J1") (pintype "passive"))
    )
    (net (code "71") (name "unconnected-(U5-NC-PadJ9)") (class "Default")
      (node (ref "U5") (pin "J9") (pinfunction "NC_J9") (pintype "passive"))
    )
    (net (code "72") (name "unconnected-(U5-NC-PadL1)") (class "Default")
      (node (ref "U5") (pin "L1") (pinfunction "NC_L1") (pintype "passive"))
    )
    (net (code "73") (name "unconnected-(U5-NC-PadL9)") (class "Default")
      (node (ref "U5") (pin "L9") (pinfunction "NC_L9") (pintype "passive"))
    )
    (net (code "74") (name "unconnected-(U5-NC-PadM7)") (class "Default")
      (node (ref "U5") (pin "M7") (pinfunction "NC_M7") (pintype "passive"))
    )
  )
)
